# PCB_Expedidora_V2_0_Rasp.net
KiCad netlist of a schematic drawn in EAGLE
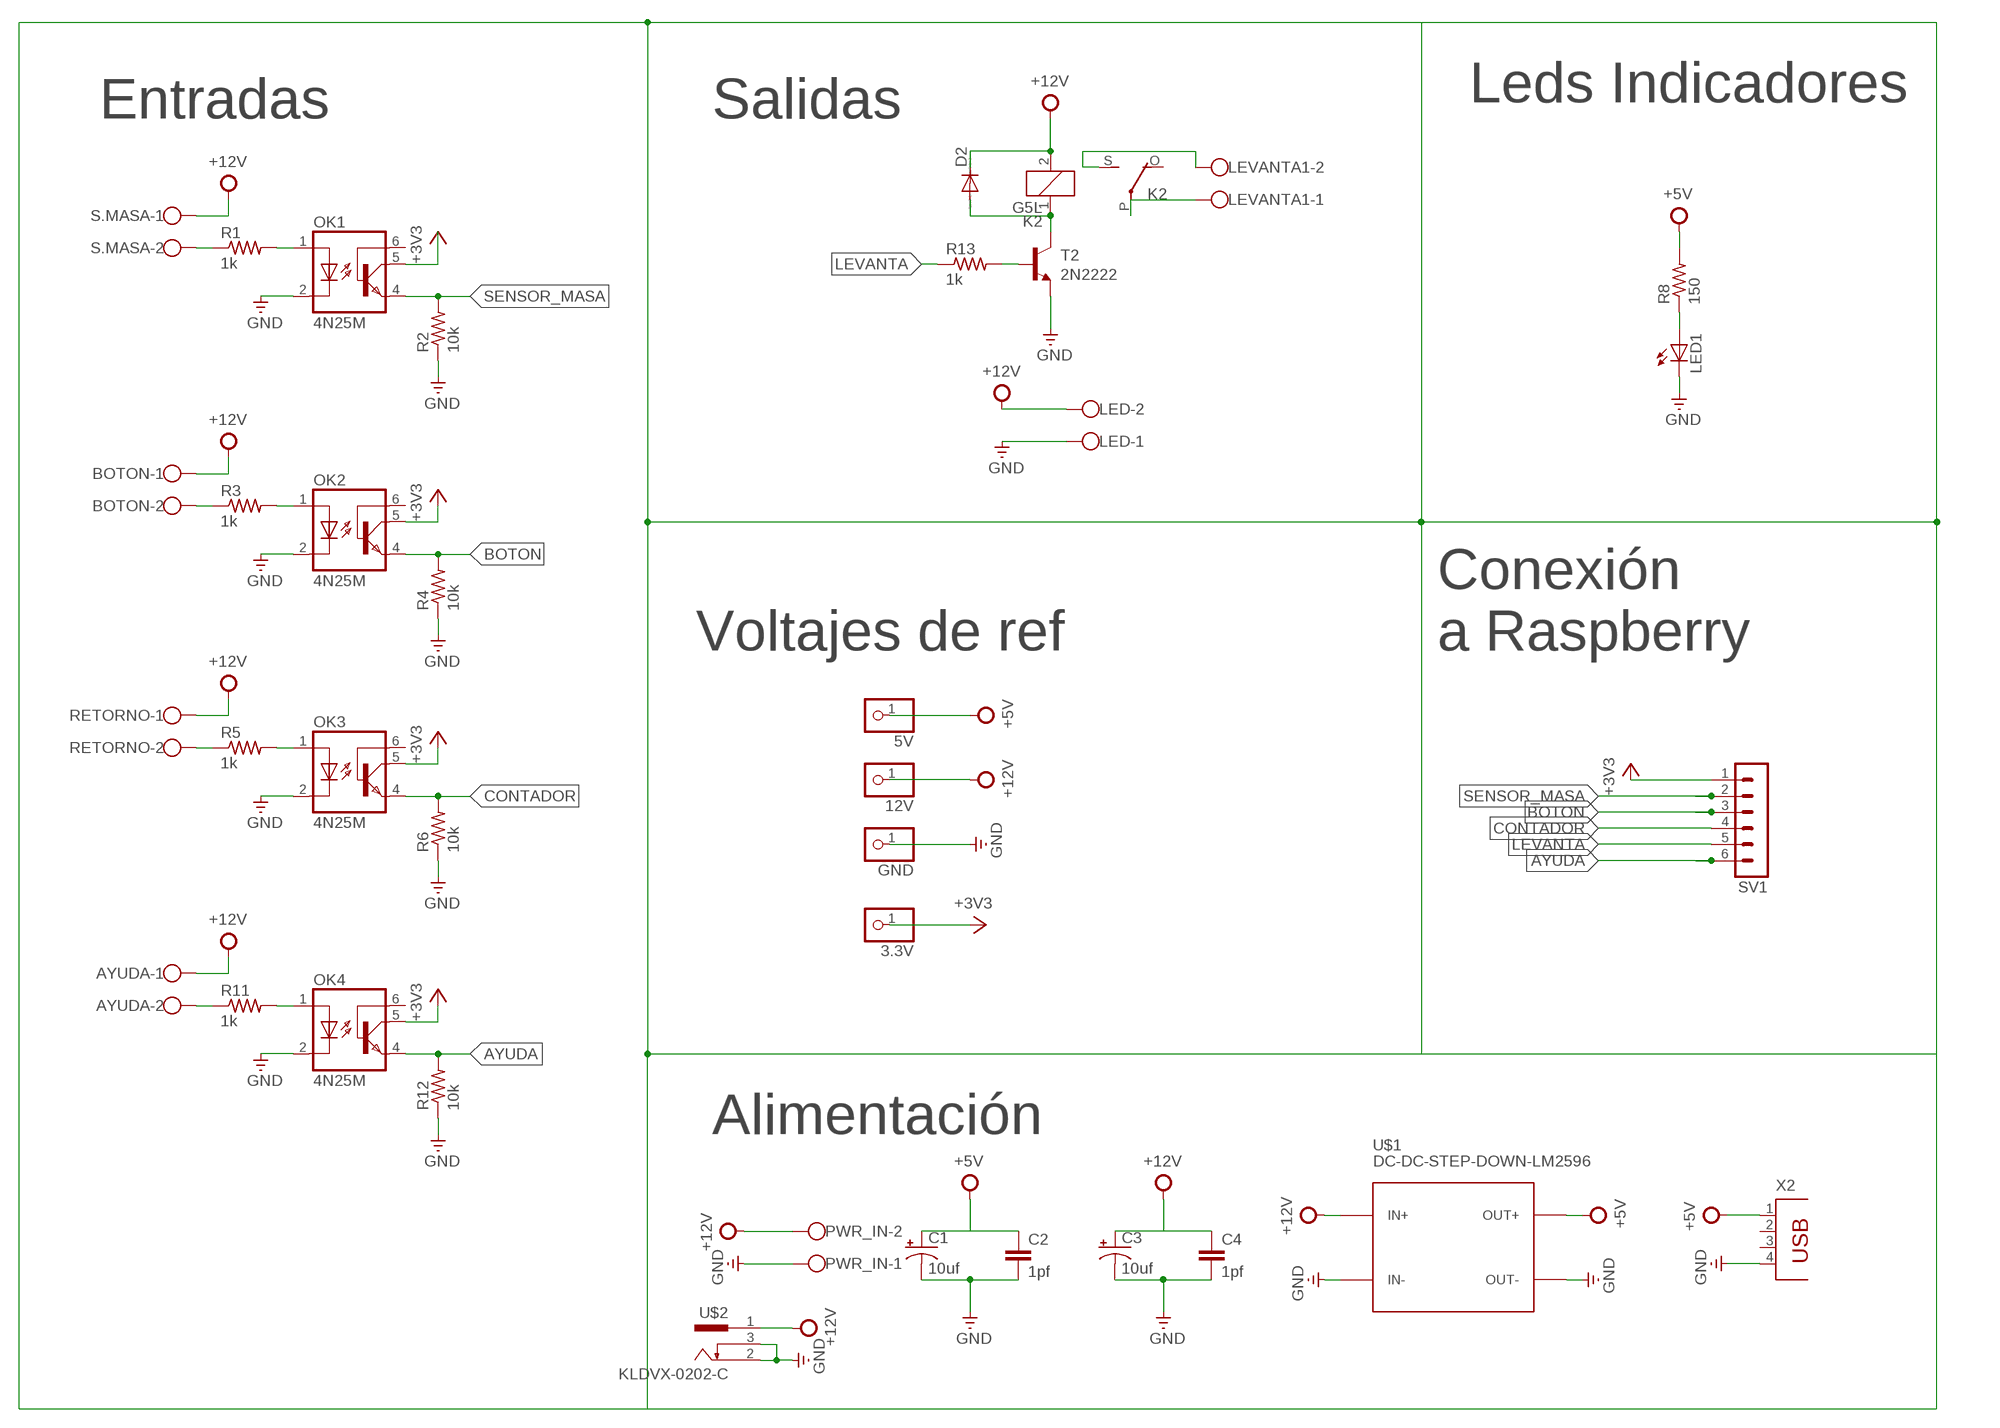
[diagram p0: schematic, sheet 1]

(export (version "E")
  (design (tool "Eeschema 10.0.6"))
  (components
    (comp (ref "3.3V")
      (value "PINHD-1X1")
      (footprint "eagle-import:1X01")
      (libsource (lib "eagle-import") (part "PINHD-1X1"))
    )
    (comp (ref "5V")
      (value "PINHD-1X1")
      (footprint "eagle-import:1X01")
      (libsource (lib "eagle-import") (part "PINHD-1X1"))
    )
    (comp (ref "12V")
      (value "PINHD-1X1")
      (footprint "eagle-import:1X01")
      (libsource (lib "eagle-import") (part "PINHD-1X1"))
    )
    (comp (ref "AYUDA")
      (value "W237-102")
      (footprint "eagle-import:W237-102")
      (fields (field (name "MPN") "237-102"))
      (libsource (lib "eagle-import") (part "W237-102"))
    )
    (comp (ref "BOTON")
      (value "W237-102")
      (footprint "eagle-import:W237-102")
      (fields (field (name "MPN") "237-102"))
      (libsource (lib "eagle-import") (part "W237-102"))
    )
    (comp (ref "C1")
      (value "10uf")
      (footprint "eagle-import:E2,5-6")
      (libsource (lib "eagle-import") (part "CPOL-USE2.5-6"))
    )
    (comp (ref "C2")
      (value "1pf")
      (footprint "eagle-import:C2.5-3")
      (libsource (lib "eagle-import") (part "C2,5-3"))
    )
    (comp (ref "C3")
      (value "10uf")
      (footprint "eagle-import:E2,5-6")
      (libsource (lib "eagle-import") (part "CPOL-USE2.5-6"))
    )
    (comp (ref "C4")
      (value "1pf")
      (footprint "eagle-import:C2.5-3")
      (libsource (lib "eagle-import") (part "C2,5-3"))
    )
    (comp (ref "D2")
      (value "1N4148DO35-7")
      (footprint "eagle-import:DO35-7")
      (libsource (lib "eagle-import") (part "1N4148DO35-7"))
    )
    (comp (ref "GND")
      (value "PINHD-1X1")
      (footprint "eagle-import:1X01")
      (libsource (lib "eagle-import") (part "PINHD-1X1"))
    )
    (comp (ref "K2")
      (value "G5L")
      (footprint "eagle-import:G5LE")
      (libsource (lib "eagle-import") (part "G5L"))
    )
    (comp (ref "LED")
      (value "W237-102")
      (footprint "eagle-import:W237-102")
      (fields (field (name "MPN") "237-102"))
      (libsource (lib "eagle-import") (part "W237-102"))
    )
    (comp (ref "LED1")
      (value "LED5MM")
      (footprint "eagle-import:LED5MM")
      (libsource (lib "eagle-import") (part "LED5MM"))
    )
    (comp (ref "LEVANTA1")
      (value "W237-102")
      (footprint "eagle-import:W237-102")
      (fields (field (name "MPN") "237-102"))
      (libsource (lib "eagle-import") (part "W237-102"))
    )
    (comp (ref "OK1")
      (value "4N25M")
      (footprint "eagle-import:DIL06")
      (fields (field (name "MPN") "4N25-M"))
      (libsource (lib "eagle-import") (part "4N?M25"))
    )
    (comp (ref "OK2")
      (value "4N25M")
      (footprint "eagle-import:DIL06")
      (fields (field (name "MPN") "4N25-M"))
      (libsource (lib "eagle-import") (part "4N?M25"))
    )
    (comp (ref "OK3")
      (value "4N25M")
      (footprint "eagle-import:DIL06")
      (fields (field (name "MPN") "4N25-M"))
      (libsource (lib "eagle-import") (part "4N?M25"))
    )
    (comp (ref "OK4")
      (value "4N25M")
      (footprint "eagle-import:DIL06")
      (fields (field (name "MPN") "4N25-M"))
      (libsource (lib "eagle-import") (part "4N?M25"))
    )
    (comp (ref "PWR_IN")
      (value "W237-102")
      (footprint "eagle-import:W237-102")
      (fields (field (name "MPN") "237-102"))
      (libsource (lib "eagle-import") (part "W237-102"))
    )
    (comp (ref "R1")
      (value "1k")
      (footprint "eagle-import:0207_7")
      (libsource (lib "eagle-import") (part "R-US_0207/7"))
    )
    (comp (ref "R2")
      (value "10k")
      (footprint "eagle-import:0207_7")
      (libsource (lib "eagle-import") (part "R-US_0207/7"))
    )
    (comp (ref "R3")
      (value "1k")
      (footprint "eagle-import:0207_7")
      (libsource (lib "eagle-import") (part "R-US_0207/7"))
    )
    (comp (ref "R4")
      (value "10k")
      (footprint "eagle-import:0207_7")
      (libsource (lib "eagle-import") (part "R-US_0207/7"))
    )
    (comp (ref "R5")
      (value "1k")
      (footprint "eagle-import:0207_7")
      (libsource (lib "eagle-import") (part "R-US_0207/7"))
    )
    (comp (ref "R6")
      (value "10k")
      (footprint "eagle-import:0207_7")
      (libsource (lib "eagle-import") (part "R-US_0207/7"))
    )
    (comp (ref "R8")
      (value "150")
      (footprint "eagle-import:0207_7")
      (libsource (lib "eagle-import") (part "R-US_0207/7"))
    )
    (comp (ref "R11")
      (value "1k")
      (footprint "eagle-import:0207_7")
      (libsource (lib "eagle-import") (part "R-US_0207/7"))
    )
    (comp (ref "R12")
      (value "10k")
      (footprint "eagle-import:0207_7")
      (libsource (lib "eagle-import") (part "R-US_0207/7"))
    )
    (comp (ref "R13")
      (value "1k")
      (footprint "eagle-import:0207_7")
      (libsource (lib "eagle-import") (part "R-US_0207/7"))
    )
    (comp (ref "RETORNO")
      (value "W237-102")
      (footprint "eagle-import:W237-102")
      (fields (field (name "MPN") "237-102"))
      (libsource (lib "eagle-import") (part "W237-102"))
    )
    (comp (ref "S.MASA")
      (value "W237-102")
      (footprint "eagle-import:W237-102")
      (fields (field (name "MPN") "237-102"))
      (libsource (lib "eagle-import") (part "W237-102"))
    )
    (comp (ref "SV1")
      (value "MA06-1")
      (footprint "eagle-import:MA06-1")
      (libsource (lib "eagle-import") (part "MA06-1"))
    )
    (comp (ref "T2")
      (value "2N2222")
      (footprint "eagle-import:TO18")
      (libsource (lib "eagle-import") (part "2N2222"))
    )
    (comp (ref "U$1")
      (value "DC-DC-STEP-DOWN-LM2596")
      (footprint "eagle-import:DC-DC-STEP-DOWN-LM2596")
      (libsource (lib "eagle-import") (part "DC-DC-STEP-DOWN-LM2596"))
    )
    (comp (ref "U$2")
      (value "KLDVX-0202-C")
      (footprint "eagle-import:KLDVX-0202-C")
      (libsource (lib "eagle-import") (part "KLDVX-0202-C"))
    )
    (comp (ref "X2")
      (value "PN87520")
      (footprint "eagle-import:PN87520")
      (libsource (lib "eagle-import") (part "PN87520"))
    )
  )
  (nets
    (net (code "1") (name "+3V3") (class "Default")
      (node (ref "3.3V") (pin "1") (pinfunction "1_1") (pintype "passive"))
      (node (ref "OK1") (pin "5") (pinfunction "COL_5") (pintype "passive"))
      (node (ref "OK2") (pin "5") (pinfunction "COL_5") (pintype "passive"))
      (node (ref "OK3") (pin "5") (pinfunction "COL_5") (pintype "passive"))
      (node (ref "OK4") (pin "5") (pinfunction "COL_5") (pintype "passive"))
      (node (ref "SV1") (pin "1") (pinfunction "1_1") (pintype "passive"))
    )
    (net (code "2") (name "+5V") (class "Default")
      (node (ref "5V") (pin "1") (pinfunction "1_1") (pintype "passive"))
      (node (ref "C1") (pin "+") (pinfunction "+_+") (pintype "passive"))
      (node (ref "C2") (pin "1") (pinfunction "1_1") (pintype "passive"))
      (node (ref "R8") (pin "2") (pinfunction "2_2") (pintype "passive"))
      (node (ref "U$1") (pin "OUT+") (pinfunction "OUT+_OUT+") (pintype "bidirectional"))
      (node (ref "X2") (pin "1") (pinfunction "1_1") (pintype "passive"))
    )
    (net (code "3") (name "+12V") (class "Default")
      (node (ref "12V") (pin "1") (pinfunction "1_1") (pintype "passive"))
      (node (ref "AYUDA") (pin "1") (pinfunction "KL_1") (pintype "passive"))
      (node (ref "BOTON") (pin "1") (pinfunction "KL_1") (pintype "passive"))
      (node (ref "C3") (pin "+") (pinfunction "+_+") (pintype "passive"))
      (node (ref "C4") (pin "1") (pinfunction "1_1") (pintype "passive"))
      (node (ref "D2") (pin "C") (pinfunction "C_C") (pintype "passive"))
      (node (ref "K2") (pin "2") (pinfunction "2_2") (pintype "passive"))
      (node (ref "LED") (pin "2") (pinfunction "KL_2") (pintype "passive"))
      (node (ref "PWR_IN") (pin "2") (pinfunction "KL_2") (pintype "passive"))
      (node (ref "RETORNO") (pin "1") (pinfunction "KL_1") (pintype "passive"))
      (node (ref "S.MASA") (pin "1") (pinfunction "KL_1") (pintype "passive"))
      (node (ref "U$1") (pin "IN+") (pinfunction "IN+_IN+") (pintype "bidirectional"))
      (node (ref "U$2") (pin "1") (pinfunction "1_1") (pintype "passive"))
    )
    (net (code "4") (name "AYUDA") (class "Default")
      (node (ref "OK4") (pin "4") (pinfunction "EMI_4") (pintype "passive"))
      (node (ref "R12") (pin "2") (pinfunction "2_2") (pintype "passive"))
      (node (ref "SV1") (pin "6") (pinfunction "6_6") (pintype "passive"))
    )
    (net (code "5") (name "BOTON") (class "Default")
      (node (ref "OK2") (pin "4") (pinfunction "EMI_4") (pintype "passive"))
      (node (ref "R4") (pin "2") (pinfunction "2_2") (pintype "passive"))
      (node (ref "SV1") (pin "3") (pinfunction "3_3") (pintype "passive"))
    )
    (net (code "6") (name "CONTADOR") (class "Default")
      (node (ref "OK3") (pin "4") (pinfunction "EMI_4") (pintype "passive"))
      (node (ref "R6") (pin "2") (pinfunction "2_2") (pintype "passive"))
      (node (ref "SV1") (pin "4") (pinfunction "4_4") (pintype "passive"))
    )
    (net (code "7") (name "GND") (class "Default")
      (node (ref "C1") (pin "-") (pinfunction "-_-") (pintype "passive"))
      (node (ref "C2") (pin "2") (pinfunction "2_2") (pintype "passive"))
      (node (ref "C3") (pin "-") (pinfunction "-_-") (pintype "passive"))
      (node (ref "C4") (pin "2") (pinfunction "2_2") (pintype "passive"))
      (node (ref "GND") (pin "1") (pinfunction "1_1") (pintype "passive"))
      (node (ref "LED") (pin "1") (pinfunction "KL_1") (pintype "passive"))
      (node (ref "LED1") (pin "K") (pinfunction "C_K") (pintype "passive"))
      (node (ref "OK1") (pin "2") (pinfunction "C_2") (pintype "passive"))
      (node (ref "OK2") (pin "2") (pinfunction "C_2") (pintype "passive"))
      (node (ref "OK3") (pin "2") (pinfunction "C_2") (pintype "passive"))
      (node (ref "OK4") (pin "2") (pinfunction "C_2") (pintype "passive"))
      (node (ref "PWR_IN") (pin "1") (pinfunction "KL_1") (pintype "passive"))
      (node (ref "R12") (pin "1") (pinfunction "1_1") (pintype "passive"))
      (node (ref "R2") (pin "1") (pinfunction "1_1") (pintype "passive"))
      (node (ref "R4") (pin "1") (pinfunction "1_1") (pintype "passive"))
      (node (ref "R6") (pin "1") (pinfunction "1_1") (pintype "passive"))
      (node (ref "T2") (pin "1") (pinfunction "E_1") (pintype "passive"))
      (node (ref "U$1") (pin "IN-") (pinfunction "IN-_IN-") (pintype "bidirectional"))
      (node (ref "U$1") (pin "OUT-") (pinfunction "OUT-_OUT-") (pintype "bidirectional"))
      (node (ref "U$2") (pin "2") (pinfunction "2_2") (pintype "passive"))
      (node (ref "U$2") (pin "3") (pinfunction "3_3") (pintype "passive"))
      (node (ref "X2") (pin "4") (pinfunction "4_4") (pintype "passive"))
    )
    (net (code "8") (name "LEVANTA") (class "Default")
      (node (ref "R13") (pin "1") (pinfunction "1_1") (pintype "passive"))
      (node (ref "SV1") (pin "5") (pinfunction "5_5") (pintype "passive"))
    )
    (net (code "9") (name "Net-(AYUDAB-KL)") (class "Default")
      (node (ref "AYUDA") (pin "2") (pinfunction "KL_2") (pintype "passive"))
      (node (ref "R11") (pin "1") (pinfunction "1_1") (pintype "passive"))
    )
    (net (code "10") (name "Net-(BOTONB-KL)") (class "Default")
      (node (ref "BOTON") (pin "2") (pinfunction "KL_2") (pintype "passive"))
      (node (ref "R3") (pin "1") (pinfunction "1_1") (pintype "passive"))
    )
    (net (code "11") (name "Net-(LED1-PadA)") (class "Default")
      (node (ref "LED1") (pin "A") (pinfunction "A_A") (pintype "passive"))
      (node (ref "R8") (pin "1") (pinfunction "1_1") (pintype "passive"))
    )
    (net (code "12") (name "Net-(LEVANTA1A-KL)") (class "Default")
      (node (ref "K2") (pin "P") (pinfunction "P_P") (pintype "passive"))
      (node (ref "LEVANTA1") (pin "1") (pinfunction "KL_1") (pintype "passive"))
    )
    (net (code "13") (name "Net-(LEVANTA1B-KL)") (class "Default")
      (node (ref "K2") (pin "S") (pinfunction "S_S") (pintype "passive"))
      (node (ref "LEVANTA1") (pin "2") (pinfunction "KL_2") (pintype "passive"))
    )
    (net (code "14") (name "Net-(OK1-A)") (class "Default")
      (node (ref "OK1") (pin "1") (pinfunction "A_1") (pintype "passive"))
      (node (ref "R1") (pin "2") (pinfunction "2_2") (pintype "passive"))
    )
    (net (code "15") (name "Net-(OK2-A)") (class "Default")
      (node (ref "OK2") (pin "1") (pinfunction "A_1") (pintype "passive"))
      (node (ref "R3") (pin "2") (pinfunction "2_2") (pintype "passive"))
    )
    (net (code "16") (name "Net-(OK3-A)") (class "Default")
      (node (ref "OK3") (pin "1") (pinfunction "A_1") (pintype "passive"))
      (node (ref "R5") (pin "2") (pinfunction "2_2") (pintype "passive"))
    )
    (net (code "17") (name "Net-(OK4-A)") (class "Default")
      (node (ref "OK4") (pin "1") (pinfunction "A_1") (pintype "passive"))
      (node (ref "R11") (pin "2") (pinfunction "2_2") (pintype "passive"))
    )
    (net (code "18") (name "Net-(RETORNOB-KL)") (class "Default")
      (node (ref "R5") (pin "1") (pinfunction "1_1") (pintype "passive"))
      (node (ref "RETORNO") (pin "2") (pinfunction "KL_2") (pintype "passive"))
    )
    (net (code "19") (name "Net-(S.MASAB-KL)") (class "Default")
      (node (ref "R1") (pin "1") (pinfunction "1_1") (pintype "passive"))
      (node (ref "S.MASA") (pin "2") (pinfunction "KL_2") (pintype "passive"))
    )
    (net (code "20") (name "Net-(T2-B)") (class "Default")
      (node (ref "R13") (pin "2") (pinfunction "2_2") (pintype "passive"))
      (node (ref "T2") (pin "2") (pinfunction "B_2") (pintype "passive"))
    )
    (net (code "21") (name "Net-(T2-C)") (class "Default")
      (node (ref "D2") (pin "A") (pinfunction "A_A") (pintype "passive"))
      (node (ref "K2") (pin "1") (pinfunction "1_1") (pintype "passive"))
      (node (ref "T2") (pin "3") (pinfunction "C_3") (pintype "passive"))
    )
    (net (code "22") (name "SENSOR_MASA") (class "Default")
      (node (ref "OK1") (pin "4") (pinfunction "EMI_4") (pintype "passive"))
      (node (ref "R2") (pin "2") (pinfunction "2_2") (pintype "passive"))
      (node (ref "SV1") (pin "2") (pinfunction "2_2") (pintype "passive"))
    )
    (net (code "23") (name "unconnected-(K2-PadO)") (class "Default")
      (node (ref "K2") (pin "O") (pinfunction "O_O") (pintype "passive"))
    )
    (net (code "24") (name "unconnected-(OK1-BAS-Pad6)") (class "Default")
      (node (ref "OK1") (pin "6") (pinfunction "BAS_6") (pintype "passive"))
    )
    (net (code "25") (name "unconnected-(OK2-BAS-Pad6)") (class "Default")
      (node (ref "OK2") (pin "6") (pinfunction "BAS_6") (pintype "passive"))
    )
    (net (code "26") (name "unconnected-(OK3-BAS-Pad6)") (class "Default")
      (node (ref "OK3") (pin "6") (pinfunction "BAS_6") (pintype "passive"))
    )
    (net (code "27") (name "unconnected-(OK4-BAS-Pad6)") (class "Default")
      (node (ref "OK4") (pin "6") (pinfunction "BAS_6") (pintype "passive"))
    )
    (net (code "28") (name "unconnected-(U$2-1-Pad1@1)") (class "Default")
      (node (ref "U$2") (pin "1@1") (pinfunction "1_1@1") (pintype "passive"))
    )
    (net (code "29") (name "unconnected-(U$2-2-Pad2@1)") (class "Default")
      (node (ref "U$2") (pin "2@1") (pinfunction "2_2@1") (pintype "passive"))
    )
    (net (code "30") (name "unconnected-(U$2-3-Pad3@1)") (class "Default")
      (node (ref "U$2") (pin "3@1") (pinfunction "3_3@1") (pintype "passive"))
    )
    (net (code "31") (name "unconnected-(X2-Pad2)") (class "Default")
      (node (ref "X2") (pin "2") (pinfunction "2_2") (pintype "passive"))
    )
    (net (code "32") (name "unconnected-(X2-Pad3)") (class "Default")
      (node (ref "X2") (pin "3") (pinfunction "3_3") (pintype "passive"))
    )
  )
)
